# sensorboard_radiation_rev1.net
KiCad netlist of a schematic drawn in EAGLE
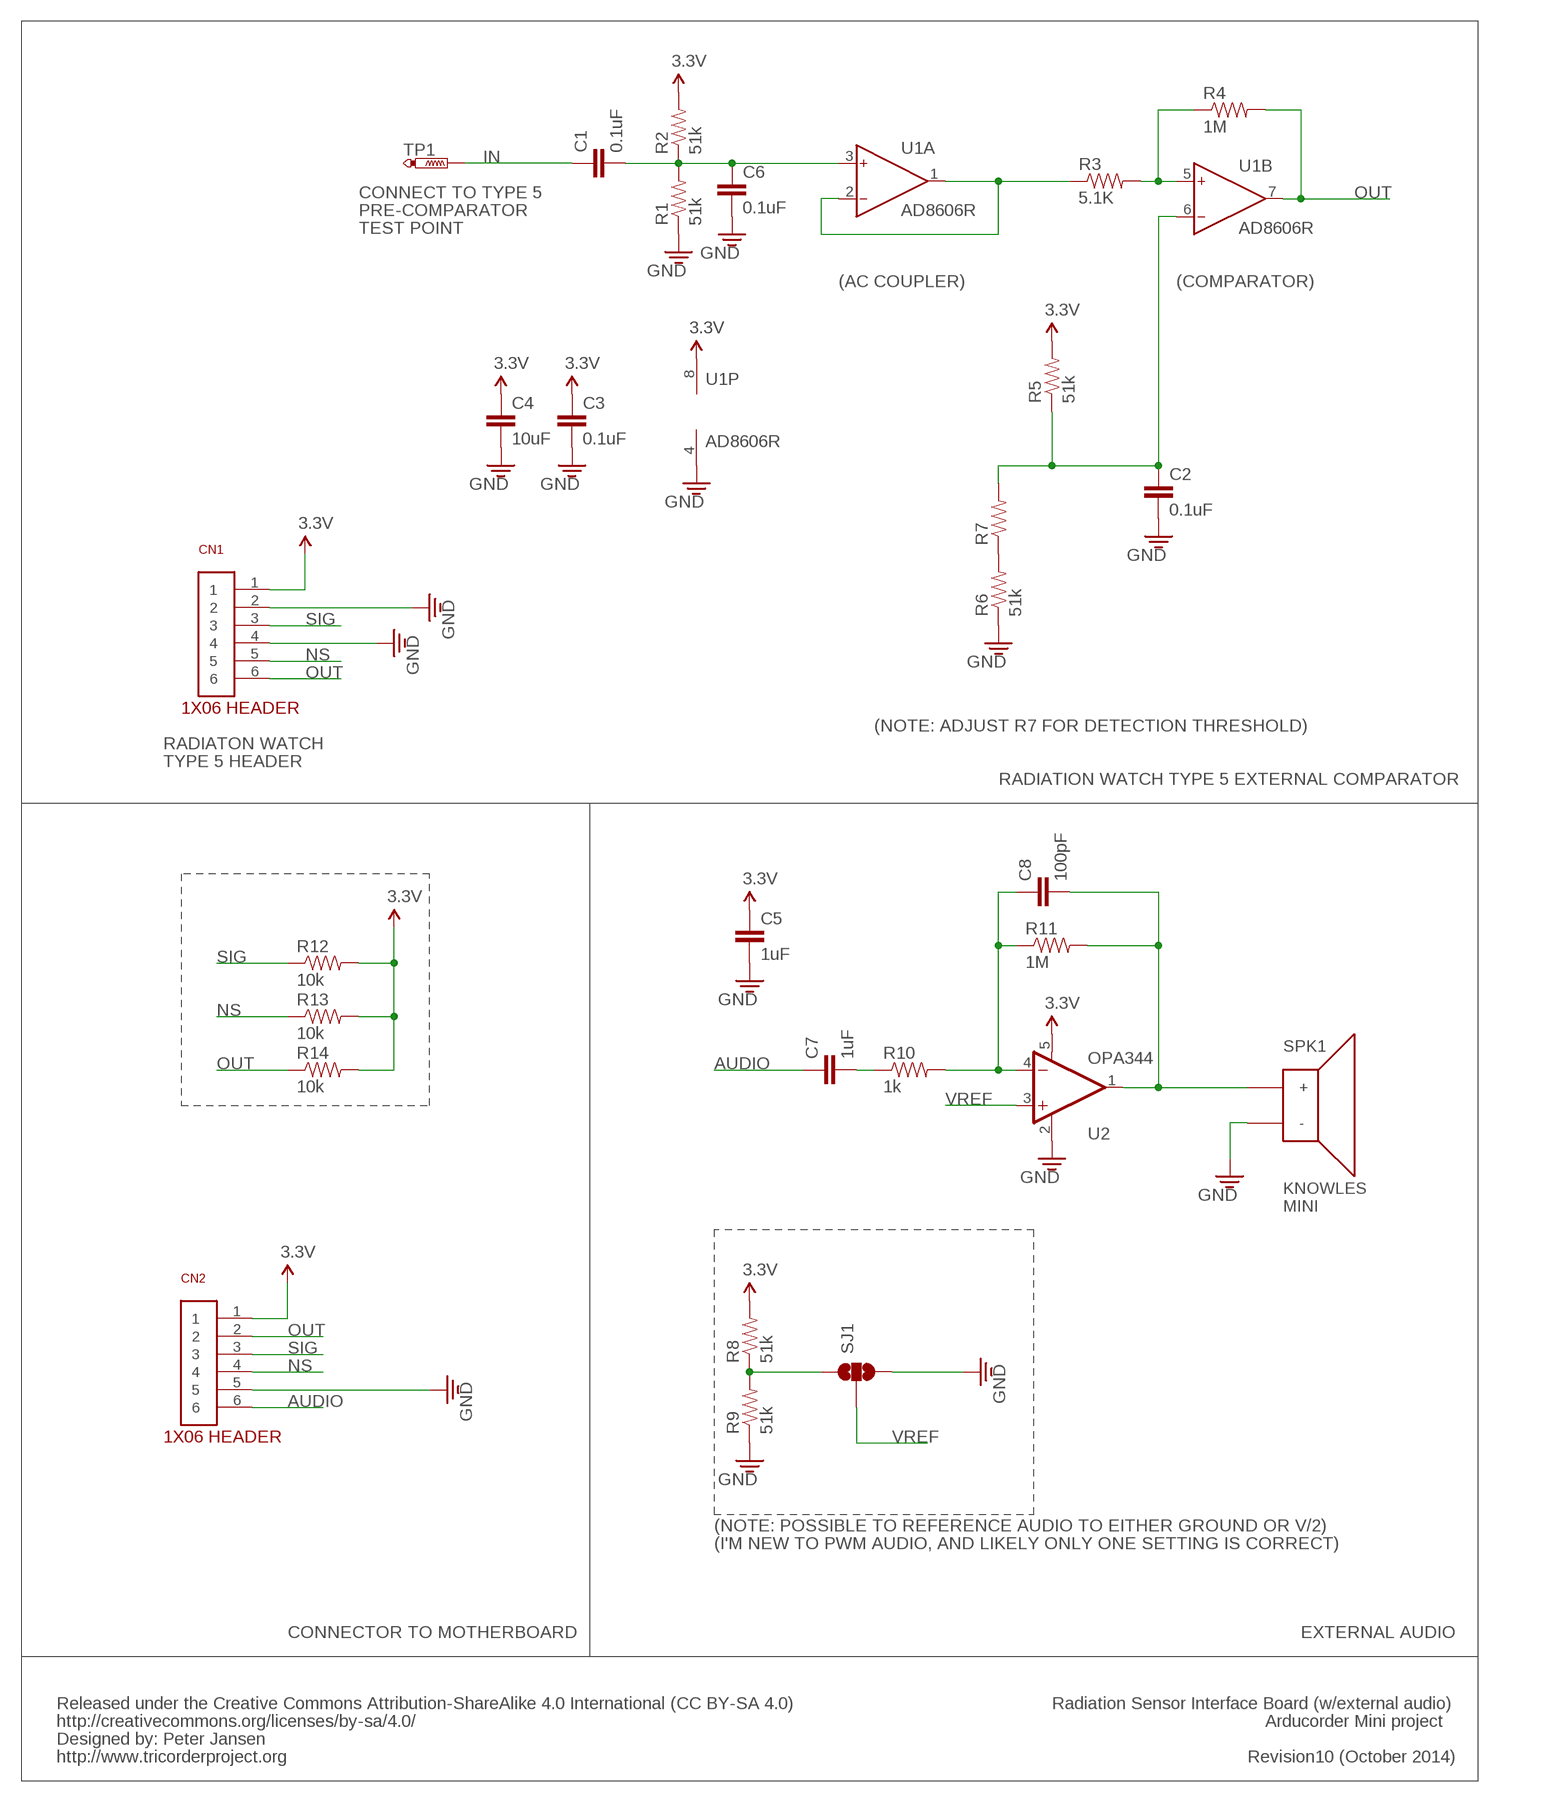
[diagram p0: schematic, sheet 1]

(export (version "E")
  (design (tool "Eeschema 10.0.6"))
  (components
    (comp (ref "C1")
      (value "0.1uF")
      (footprint "eagle-import:0603")
      (libsource (lib "eagle-import") (part "CAP0603"))
    )
    (comp (ref "C2")
      (value "0.1uF")
      (footprint "eagle-import:0603")
      (libsource (lib "eagle-import") (part "CAP0603"))
    )
    (comp (ref "C3")
      (value "0.1uF")
      (footprint "eagle-import:0603")
      (libsource (lib "eagle-import") (part "CAP0603"))
    )
    (comp (ref "C4")
      (value "10uF")
      (footprint "eagle-import:0603")
      (libsource (lib "eagle-import") (part "CAP0603"))
    )
    (comp (ref "C5")
      (value "1uF")
      (footprint "eagle-import:0603")
      (libsource (lib "eagle-import") (part "notes_mark5a_CAP0603"))
    )
    (comp (ref "C6")
      (value "0.1uF")
      (footprint "eagle-import:0603")
      (libsource (lib "eagle-import") (part "CAP0603"))
    )
    (comp (ref "C7")
      (value "1uF")
      (footprint "eagle-import:0603")
      (libsource (lib "eagle-import") (part "notes_mark5a_CAP0603"))
    )
    (comp (ref "C8")
      (value "100pF")
      (footprint "eagle-import:0603")
      (libsource (lib "eagle-import") (part "notes_mark5a_CAP0603"))
    )
    (comp (ref "CN1")
      (value "1X06")
      (footprint "eagle-import:1X06")
      (libsource (lib "eagle-import") (part "1X06"))
    )
    (comp (ref "CN2")
      (value "PHT-106-01-L-S")
      (footprint "eagle-import:1X06")
      (libsource (lib "eagle-import") (part "arm1a_1X06"))
    )
    (comp (ref "R1")
      (value "51k")
      (footprint "eagle-import:0603")
      (libsource (lib "eagle-import") (part "RESISTOR0603"))
    )
    (comp (ref "R2")
      (value "51k")
      (footprint "eagle-import:0603")
      (libsource (lib "eagle-import") (part "RESISTOR0603"))
    )
    (comp (ref "R3")
      (value "5.1K")
      (footprint "eagle-import:0603")
      (libsource (lib "eagle-import") (part "RESISTOR0603"))
    )
    (comp (ref "R4")
      (value "1M")
      (footprint "eagle-import:0603")
      (libsource (lib "eagle-import") (part "RESISTOR0603"))
    )
    (comp (ref "R5")
      (value "51k")
      (footprint "eagle-import:0603")
      (libsource (lib "eagle-import") (part "RESISTOR0603"))
    )
    (comp (ref "R6")
      (value "51k")
      (footprint "eagle-import:0603")
      (libsource (lib "eagle-import") (part "RESISTOR0603"))
    )
    (comp (ref "R7")
      (value "RESISTOR0603")
      (footprint "eagle-import:0603")
      (libsource (lib "eagle-import") (part "RESISTOR0603"))
    )
    (comp (ref "R8")
      (value "51k")
      (footprint "eagle-import:0603")
      (libsource (lib "eagle-import") (part "notes_mark5a_RESISTOR0603"))
    )
    (comp (ref "R9")
      (value "51k")
      (footprint "eagle-import:0603")
      (libsource (lib "eagle-import") (part "notes_mark5a_RESISTOR0603"))
    )
    (comp (ref "R10")
      (value "1k")
      (footprint "eagle-import:0603")
      (libsource (lib "eagle-import") (part "notes_mark5a_RESISTOR0603"))
    )
    (comp (ref "R11")
      (value "1M")
      (footprint "eagle-import:0603")
      (libsource (lib "eagle-import") (part "notes_mark5a_RESISTOR0603"))
    )
    (comp (ref "R12")
      (value "10k")
      (footprint "eagle-import:0603")
      (libsource (lib "eagle-import") (part "RESISTOR0603"))
    )
    (comp (ref "R13")
      (value "10k")
      (footprint "eagle-import:0603")
      (libsource (lib "eagle-import") (part "RESISTOR0603"))
    )
    (comp (ref "R14")
      (value "10k")
      (footprint "eagle-import:0603")
      (libsource (lib "eagle-import") (part "RESISTOR0603"))
    )
    (comp (ref "SJ1")
      (value "SOLDERJUMPER_2WAYPASTE1&2")
      (footprint "eagle-import:SJ_3_PASTE1&2")
      (libsource (lib "eagle-import") (part "SOLDERJUMPER_2WAYPASTE1&2"))
    )
    (comp (ref "SPK1")
      (value "KNOWLES-MINI-SPEAKER")
      (footprint "eagle-import:KNOWLES-MINI-SPEAKER")
      (libsource (lib "eagle-import") (part "KNOWLES-MINI-SPEAKER"))
    )
    (comp (ref "TP1")
      (value "PTR1PAD1-13")
      (footprint "eagle-import:P1-13")
      (libsource (lib "eagle-import") (part "PTR1PAD1-13"))
    )
    (comp (ref "U1")
      (value "AD8606R")
      (footprint "eagle-import:SO8")
      (fields (field (name "MPN") "AD8607ARMZ-R2"))
      (libsource (lib "eagle-import") (part "AD8607R"))
    )
    (comp (ref "U2")
      (value "OPA344")
      (footprint "eagle-import:SOT23-5")
      (libsource (lib "eagle-import") (part "OPA344"))
    )
  )
  (nets
    (net (code "1") (name "/AUDIO") (class "Default")
      (node (ref "C7") (pin "1") (pinfunction "1_1") (pintype "passive"))
      (node (ref "CN2") (pin "6") (pinfunction "6_6") (pintype "bidirectional"))
    )
    (net (code "2") (name "/IN") (class "Default")
      (node (ref "C1") (pin "1") (pinfunction "1_1") (pintype "passive"))
      (node (ref "TP1") (pin "TP") (pinfunction "TP_TP") (pintype "input"))
    )
    (net (code "3") (name "/NS") (class "Default")
      (node (ref "CN1") (pin "5") (pinfunction "5_5") (pintype "bidirectional"))
      (node (ref "CN2") (pin "4") (pinfunction "4_4") (pintype "bidirectional"))
      (node (ref "R13") (pin "1") (pinfunction "1_1") (pintype "passive"))
    )
    (net (code "4") (name "/OUT") (class "Default")
      (node (ref "CN1") (pin "6") (pinfunction "6_6") (pintype "bidirectional"))
      (node (ref "CN2") (pin "2") (pinfunction "2_2") (pintype "bidirectional"))
      (node (ref "R14") (pin "1") (pinfunction "1_1") (pintype "passive"))
      (node (ref "R4") (pin "2") (pinfunction "2_2") (pintype "passive"))
      (node (ref "U1") (pin "7") (pinfunction "OUT_7") (pintype "output"))
    )
    (net (code "5") (name "/SIG") (class "Default")
      (node (ref "CN1") (pin "3") (pinfunction "3_3") (pintype "bidirectional"))
      (node (ref "CN2") (pin "3") (pinfunction "3_3") (pintype "bidirectional"))
      (node (ref "R12") (pin "1") (pinfunction "1_1") (pintype "passive"))
    )
    (net (code "6") (name "/VREF") (class "Default")
      (node (ref "SJ1") (pin "2") (pinfunction "2_2") (pintype "passive"))
      (node (ref "U2") (pin "3") (pinfunction "+IN_3") (pintype "input"))
    )
    (net (code "7") (name "3.3V") (class "Default")
      (node (ref "C3") (pin "1") (pinfunction "1_1") (pintype "passive"))
      (node (ref "C4") (pin "1") (pinfunction "1_1") (pintype "passive"))
      (node (ref "C5") (pin "1") (pinfunction "1_1") (pintype "passive"))
      (node (ref "CN1") (pin "1") (pinfunction "1_1") (pintype "bidirectional"))
      (node (ref "CN2") (pin "1") (pinfunction "1_1") (pintype "bidirectional"))
      (node (ref "R12") (pin "2") (pinfunction "2_2") (pintype "passive"))
      (node (ref "R13") (pin "2") (pinfunction "2_2") (pintype "passive"))
      (node (ref "R14") (pin "2") (pinfunction "2_2") (pintype "passive"))
      (node (ref "R2") (pin "2") (pinfunction "2_2") (pintype "passive"))
      (node (ref "R5") (pin "2") (pinfunction "2_2") (pintype "passive"))
      (node (ref "R8") (pin "2") (pinfunction "2_2") (pintype "passive"))
      (node (ref "U1") (pin "8") (pinfunction "V+_8") (pintype "power_in"))
      (node (ref "U2") (pin "5") (pinfunction "V+_5") (pintype "power_in"))
    )
    (net (code "8") (name "GND") (class "Default")
      (node (ref "C2") (pin "2") (pinfunction "2_2") (pintype "passive"))
      (node (ref "C3") (pin "2") (pinfunction "2_2") (pintype "passive"))
      (node (ref "C4") (pin "2") (pinfunction "2_2") (pintype "passive"))
      (node (ref "C5") (pin "2") (pinfunction "2_2") (pintype "passive"))
      (node (ref "C6") (pin "2") (pinfunction "2_2") (pintype "passive"))
      (node (ref "CN1") (pin "2") (pinfunction "2_2") (pintype "bidirectional"))
      (node (ref "CN1") (pin "4") (pinfunction "4_4") (pintype "bidirectional"))
      (node (ref "CN2") (pin "5") (pinfunction "5_5") (pintype "bidirectional"))
      (node (ref "R1") (pin "1") (pinfunction "1_1") (pintype "passive"))
      (node (ref "R6") (pin "1") (pinfunction "1_1") (pintype "passive"))
      (node (ref "R9") (pin "1") (pinfunction "1_1") (pintype "passive"))
      (node (ref "SJ1") (pin "3") (pinfunction "3_3") (pintype "passive"))
      (node (ref "SPK1") (pin "NEG") (pinfunction "-_NEG") (pintype "bidirectional"))
      (node (ref "U1") (pin "4") (pinfunction "V-_4") (pintype "power_in"))
      (node (ref "U2") (pin "2") (pinfunction "V-_2") (pintype "power_in"))
    )
    (net (code "9") (name "Net-(C7-Pad2)") (class "Default")
      (node (ref "C7") (pin "2") (pinfunction "2_2") (pintype "passive"))
      (node (ref "R10") (pin "1") (pinfunction "1_1") (pintype "passive"))
    )
    (net (code "10") (name "Net-(R6-Pad2)") (class "Default")
      (node (ref "R6") (pin "2") (pinfunction "2_2") (pintype "passive"))
      (node (ref "R7") (pin "1") (pinfunction "1_1") (pintype "passive"))
    )
    (net (code "11") (name "Net-(R8-Pad1)") (class "Default")
      (node (ref "R8") (pin "1") (pinfunction "1_1") (pintype "passive"))
      (node (ref "R9") (pin "2") (pinfunction "2_2") (pintype "passive"))
      (node (ref "SJ1") (pin "1") (pinfunction "1_1") (pintype "passive"))
    )
    (net (code "12") (name "Net-(SPK1-+)") (class "Default")
      (node (ref "C8") (pin "2") (pinfunction "2_2") (pintype "passive"))
      (node (ref "R11") (pin "2") (pinfunction "2_2") (pintype "passive"))
      (node (ref "SPK1") (pin "POS") (pinfunction "+_POS") (pintype "bidirectional"))
      (node (ref "U2") (pin "1") (pinfunction "OUT_1") (pintype "output"))
    )
    (net (code "13") (name "Net-(U1A-IN+)") (class "Default")
      (node (ref "C1") (pin "2") (pinfunction "2_2") (pintype "passive"))
      (node (ref "C6") (pin "1") (pinfunction "1_1") (pintype "passive"))
      (node (ref "R1") (pin "2") (pinfunction "2_2") (pintype "passive"))
      (node (ref "R2") (pin "1") (pinfunction "1_1") (pintype "passive"))
      (node (ref "U1") (pin "3") (pinfunction "IN+_3") (pintype "input"))
    )
    (net (code "14") (name "Net-(U1A-IN-)") (class "Default")
      (node (ref "R3") (pin "1") (pinfunction "1_1") (pintype "passive"))
      (node (ref "U1") (pin "1") (pinfunction "OUT_1") (pintype "output"))
      (node (ref "U1") (pin "2") (pinfunction "IN-_2") (pintype "input"))
    )
    (net (code "15") (name "Net-(U1B-IN+)") (class "Default")
      (node (ref "R3") (pin "2") (pinfunction "2_2") (pintype "passive"))
      (node (ref "R4") (pin "1") (pinfunction "1_1") (pintype "passive"))
      (node (ref "U1") (pin "5") (pinfunction "IN+_5") (pintype "input"))
    )
    (net (code "16") (name "Net-(U1B-IN-)") (class "Default")
      (node (ref "C2") (pin "1") (pinfunction "1_1") (pintype "passive"))
      (node (ref "R5") (pin "1") (pinfunction "1_1") (pintype "passive"))
      (node (ref "R7") (pin "2") (pinfunction "2_2") (pintype "passive"))
      (node (ref "U1") (pin "6") (pinfunction "IN-_6") (pintype "input"))
    )
    (net (code "17") (name "Net-(U2--IN)") (class "Default")
      (node (ref "C8") (pin "1") (pinfunction "1_1") (pintype "passive"))
      (node (ref "R10") (pin "2") (pinfunction "2_2") (pintype "passive"))
      (node (ref "R11") (pin "1") (pinfunction "1_1") (pintype "passive"))
      (node (ref "U2") (pin "4") (pinfunction "-IN_4") (pintype "input"))
    )
  )
)
